# SCH_Hacker-Card-Sigma_2025-04-10.net
KiCad netlist of a schematic drawn in EasyEDA
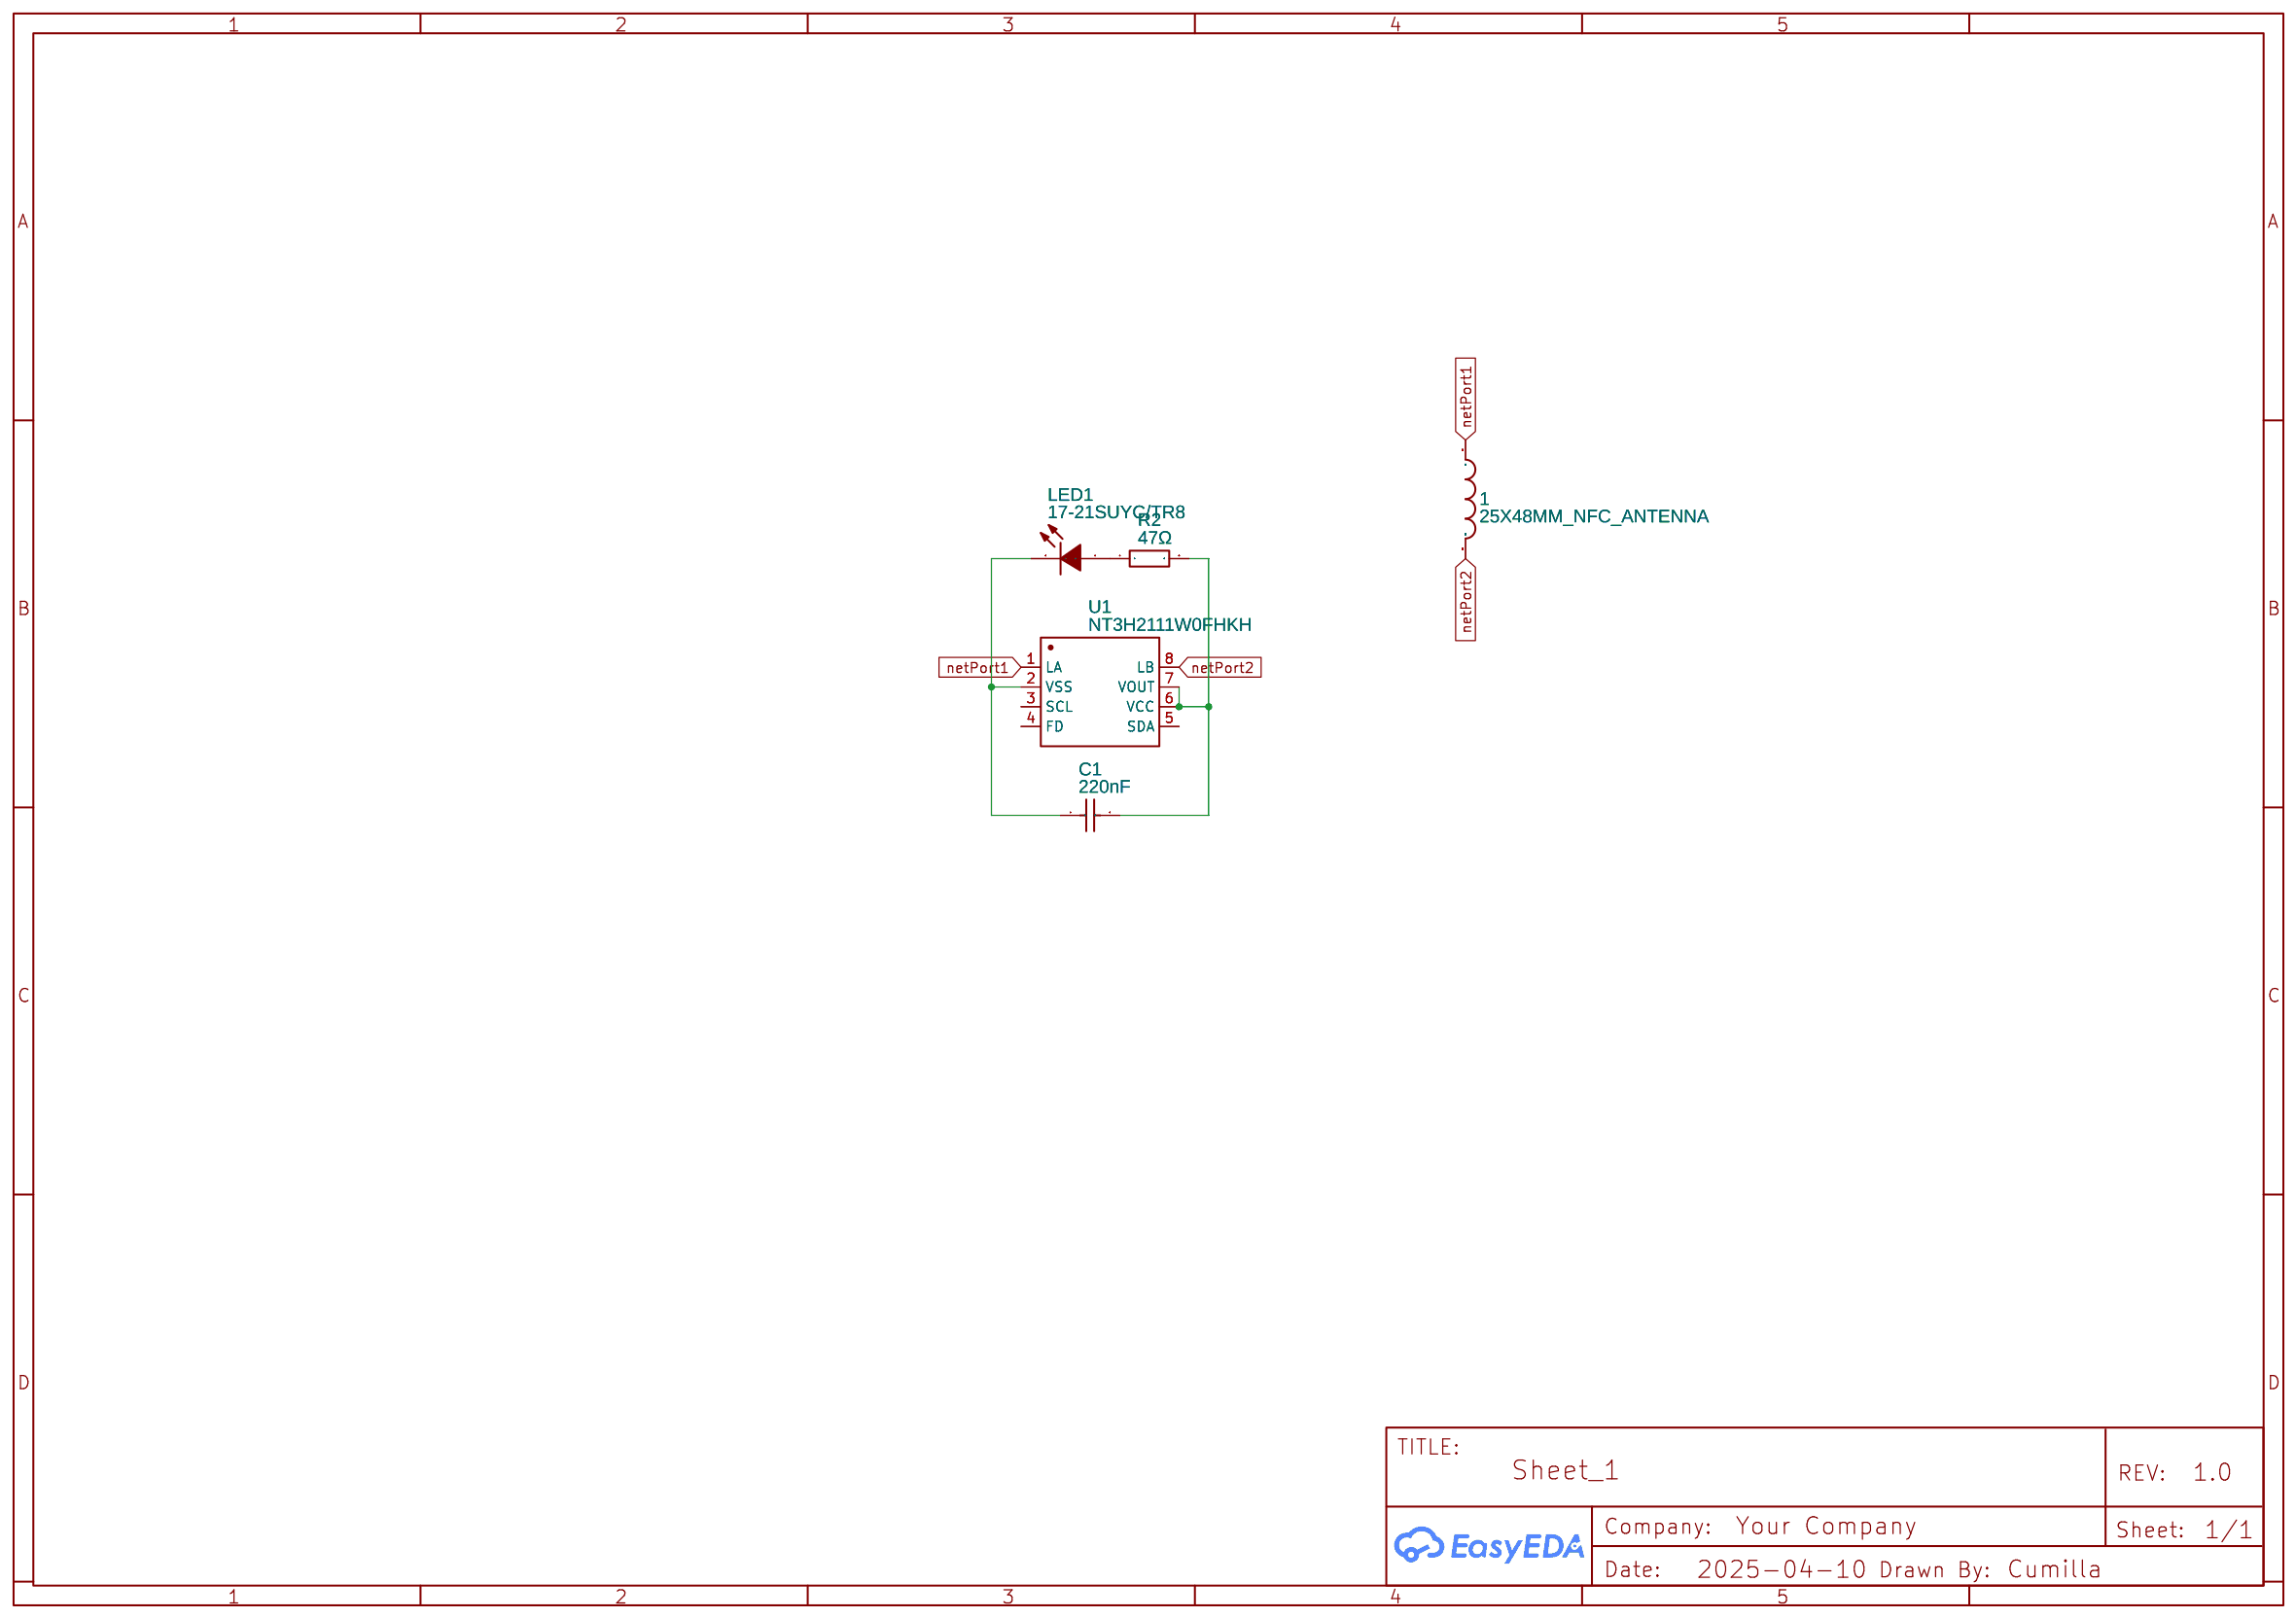
[diagram p0: schematic sheet]

(export (version "E")
  (design (tool "Eeschema 10.0.6"))
  (components
    (comp (ref "1") (value "25X48MM_NFC_ANTENNA") (libsource (lib "") (part "25X48MM_NFC_ANTENNA")))
    (comp (ref "C1")
      (value "220nF")
      (fields
        (field (name "Manufacturer Part") "CL05B224KO5NNNC")
        (field (name "Manufacturer") "SAMSUNG(三星)")
      )
      (libsource (lib "") (part "CL05B224KO5NNNC"))
    )
    (comp (ref "LED1")
      (value "17-21SUYC/TR8")
      (fields (field (name "Manufacturer Part") "KT-0805黄灯") (field (name "Manufacturer") "KENTO"))
      (libsource (lib "") (part "17-21SUYC/TR8"))
    )
    (comp (ref "R2")
      (value "47Ω")
      (fields
        (field (name "Manufacturer Part") "0603WAF470JT5E")
        (field (name "Manufacturer") "UNI-ROYAL(厚声)")
      )
      (libsource (lib "") (part "0603WAF470JT5E"))
    )
    (comp (ref "U1")
      (value "NT3H2111W0FHKH")
      (fields (field (name "Manufacturer") "NXP(恩智浦)"))
      (libsource (lib "") (part "NT3H2111W0FHKH"))
    )
  )
  (nets
    (net (code "1") (name "Net-(LED1-+)") (class "Default")
      (node (ref "LED1") (pin "1") (pinfunction "+_1") (pintype "unspecified"))
      (node (ref "R2") (pin "1") (pinfunction "1_1") (pintype "input"))
    )
    (net (code "2") (name "Net-(LED1--)") (class "Default")
      (node (ref "C1") (pin "1") (pinfunction "1_1") (pintype "input"))
      (node (ref "LED1") (pin "2") (pinfunction "-_2") (pintype "unspecified"))
      (node (ref "U1") (pin "2") (pinfunction "VSS_2") (pintype "unspecified"))
    )
    (net (code "3") (name "Net-(U1-VCC)") (class "Default")
      (node (ref "C1") (pin "2") (pinfunction "2_2") (pintype "input"))
      (node (ref "R2") (pin "2") (pinfunction "2_2") (pintype "input"))
      (node (ref "U1") (pin "6") (pinfunction "VCC_6") (pintype "unspecified"))
      (node (ref "U1") (pin "7") (pinfunction "VOUT_7") (pintype "unspecified"))
    )
    (net (code "4") (name "netPort1") (class "Default")
      (node (ref "1") (pin "P$1") (pinfunction "P$1_P$1") (pintype "bidirectional"))
      (node (ref "U1") (pin "1") (pinfunction "LA_1") (pintype "unspecified"))
    )
    (net (code "5") (name "netPort2") (class "Default")
      (node (ref "1") (pin "P$2") (pinfunction "P$2_P$2") (pintype "bidirectional"))
      (node (ref "U1") (pin "8") (pinfunction "LB_8") (pintype "unspecified"))
    )
    (net (code "6") (name "unconnected-(U1-FD-Pad4)") (class "Default")
      (node (ref "U1") (pin "4") (pinfunction "FD_4") (pintype "unspecified"))
    )
    (net (code "7") (name "unconnected-(U1-SCL-Pad3)") (class "Default")
      (node (ref "U1") (pin "3") (pinfunction "SCL_3") (pintype "unspecified"))
    )
    (net (code "8") (name "unconnected-(U1-SDA-Pad5)") (class "Default")
      (node (ref "U1") (pin "5") (pinfunction "SDA_5") (pintype "unspecified"))
    )
  )
)
